# terminator.net
KiCad netlist of a schematic drawn in EAGLE
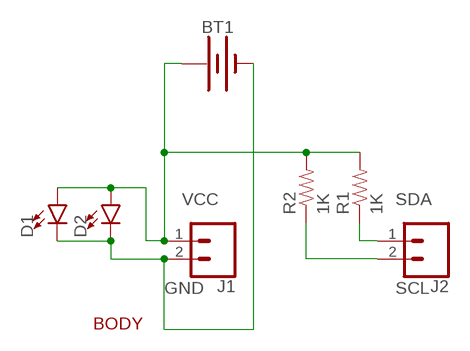
[diagram p0: schematic, sheet 1]

(export (version "E")
  (design (tool "Eeschema 10.0.6"))
  (components
    (comp (ref "BT1")
      (value "BATTERY-20MM_SMD")
      (footprint "eagle-import:BATTCON_20MM")
      (libsource (lib "eagle-import") (part "BATTERY-20MM_SMD"))
    )
    (comp (ref "D1")
      (value "LED3MM")
      (footprint "eagle-import:LED_3MM")
      (libsource (lib "eagle-import") (part "LED3MM"))
    )
    (comp (ref "D2")
      (value "LED3MM")
      (footprint "eagle-import:LED_3MM")
      (libsource (lib "eagle-import") (part "LED3MM"))
    )
    (comp (ref "J1")
      (value "CONN_02LOCK")
      (footprint "eagle-import:1X02_LOCK")
      (libsource (lib "eagle-import") (part "CONN_02LOCK"))
    )
    (comp (ref "J2")
      (value "CONN_02LOCK")
      (footprint "eagle-import:1X02_LOCK")
      (libsource (lib "eagle-import") (part "CONN_02LOCK"))
    )
    (comp (ref "R1")
      (value "1K")
      (footprint "eagle-import:AXIAL-0.3EZ")
      (libsource (lib "eagle-import") (part "1KOHM-1/4W-1%(PTH)HORIZ-KIT"))
    )
    (comp (ref "R2")
      (value "1K")
      (footprint "eagle-import:AXIAL-0.3EZ")
      (libsource (lib "eagle-import") (part "1KOHM-1/4W-1%(PTH)HORIZ-KIT"))
    )
    (comp (ref "U$1")
      (value "BODYTERMINATOR")
      (footprint "eagle-import:TERMINATOR")
      (libsource (lib "eagle-import") (part "BODYTERMINATOR"))
    )
  )
  (nets
    (net (code "1") (name "/GND") (class "Default")
      (node (ref "BT1") (pin "2") (pinfunction "-_2") (pintype "power_in"))
      (node (ref "D1") (pin "K") (pinfunction "C_K") (pintype "passive"))
      (node (ref "D2") (pin "K") (pinfunction "C_K") (pintype "passive"))
      (node (ref "J1") (pin "2") (pinfunction "2_2") (pintype "passive"))
    )
    (net (code "2") (name "/SCL") (class "Default")
      (node (ref "J2") (pin "2") (pinfunction "2_2") (pintype "passive"))
      (node (ref "R2") (pin "P$1") (pinfunction "1_P$1") (pintype "passive"))
    )
    (net (code "3") (name "/SDA") (class "Default")
      (node (ref "J2") (pin "1") (pinfunction "1_1") (pintype "passive"))
      (node (ref "R1") (pin "P$1") (pinfunction "1_P$1") (pintype "passive"))
    )
    (net (code "4") (name "/VCC") (class "Default")
      (node (ref "BT1") (pin "1") (pinfunction "+_1") (pintype "power_in"))
      (node (ref "D1") (pin "A") (pinfunction "A_A") (pintype "passive"))
      (node (ref "D2") (pin "A") (pinfunction "A_A") (pintype "passive"))
      (node (ref "J1") (pin "1") (pinfunction "1_1") (pintype "passive"))
      (node (ref "R1") (pin "P$2") (pinfunction "2_P$2") (pintype "passive"))
      (node (ref "R2") (pin "P$2") (pinfunction "2_P$2") (pintype "passive"))
    )
  )
)
